# Adafruit_3_5_inch_480x320_Capacitive_Tou.net
KiCad netlist of a schematic drawn in EAGLE
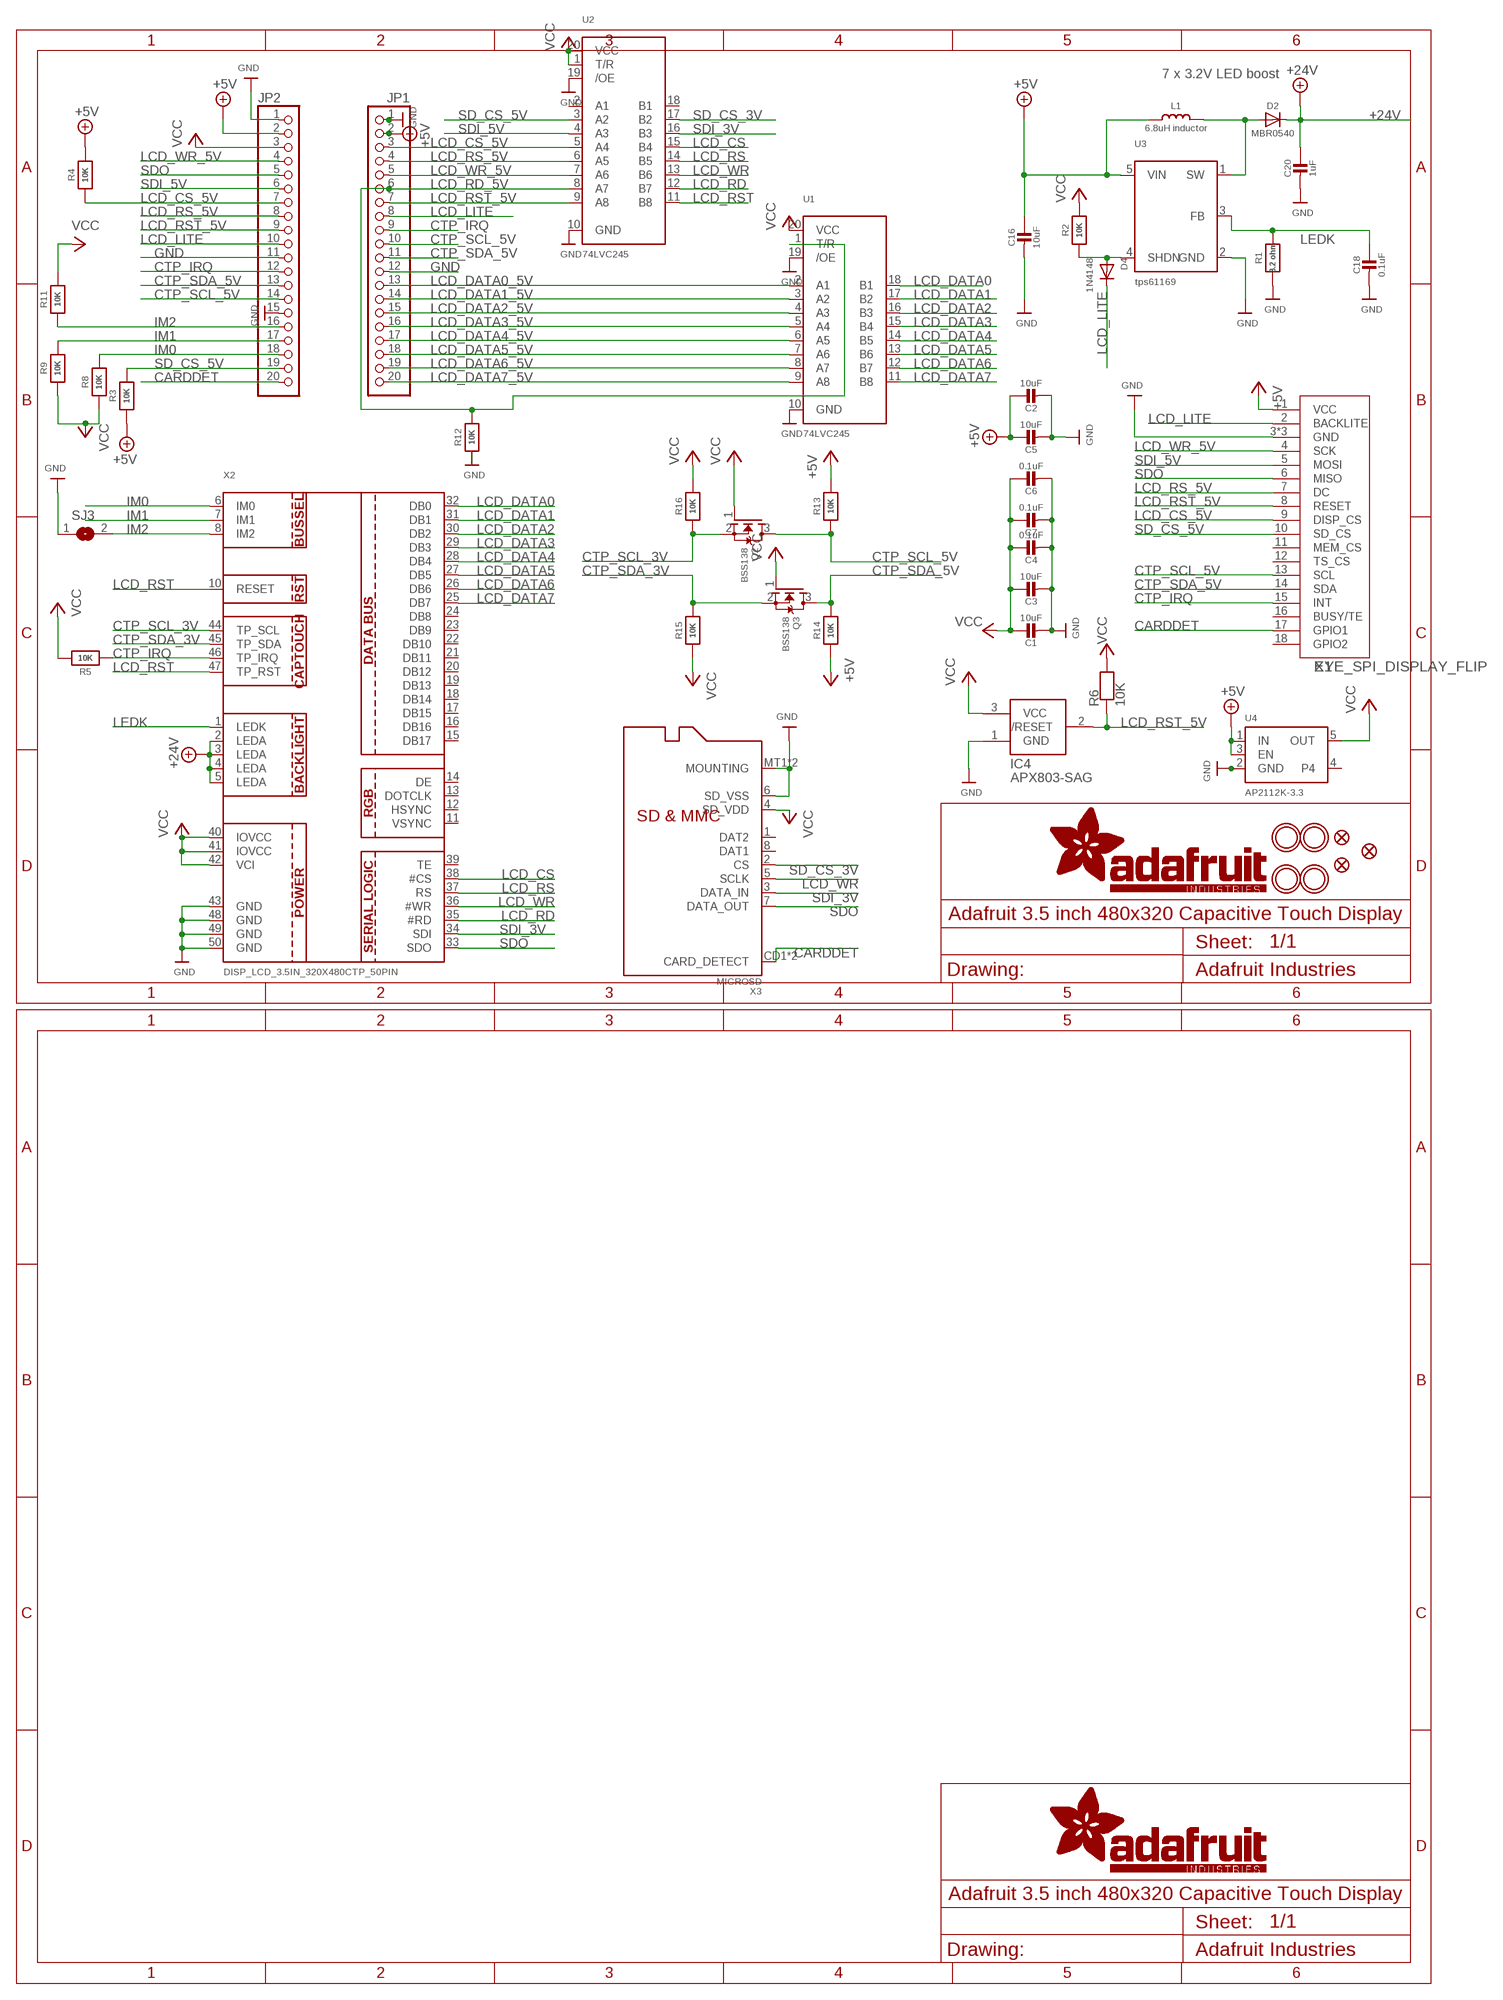
[diagram p0: schematic, sheet 1]

(export (version "E")
  (design (tool "Eeschema 10.0.6"))
  (components
    (comp (ref "C1")
      (value "10uF")
      (footprint "eagle-import:0805-NO")
      (libsource (lib "eagle-import") (part "CAP_CERAMIC0805-NOOUTLINE"))
    )
    (comp (ref "C2")
      (value "10uF")
      (footprint "eagle-import:0805-NO")
      (libsource (lib "eagle-import") (part "CAP_CERAMIC0805-NOOUTLINE"))
    )
    (comp (ref "C3")
      (value "10uF")
      (footprint "eagle-import:0805-NO")
      (libsource (lib "eagle-import") (part "CAP_CERAMIC0805-NOOUTLINE"))
    )
    (comp (ref "C4")
      (value "0.1uF")
      (footprint "eagle-import:0603-NO")
      (libsource (lib "eagle-import") (part "CAP_CERAMIC0603_NO"))
    )
    (comp (ref "C5")
      (value "10uF")
      (footprint "eagle-import:0805-NO")
      (libsource (lib "eagle-import") (part "CAP_CERAMIC0805-NOOUTLINE"))
    )
    (comp (ref "C6")
      (value "0.1uF")
      (footprint "eagle-import:0603-NO")
      (libsource (lib "eagle-import") (part "CAP_CERAMIC0603_NO"))
    )
    (comp (ref "C7")
      (value "0.1uF")
      (footprint "eagle-import:0603-NO")
      (libsource (lib "eagle-import") (part "CAP_CERAMIC0603_NO"))
    )
    (comp (ref "C16")
      (value "10uF")
      (footprint "eagle-import:0805-NO")
      (libsource (lib "eagle-import") (part "CAP_CERAMIC0805-NOOUTLINE"))
    )
    (comp (ref "C18")
      (value "0.1uF")
      (footprint "eagle-import:0603-NO")
      (libsource (lib "eagle-import") (part "CAP_CERAMIC0603_NO"))
    )
    (comp (ref "C20")
      (value "1uF")
      (footprint "eagle-import:0805-NO")
      (libsource (lib "eagle-import") (part "CAP_CERAMIC0805-NOOUTLINE"))
    )
    (comp (ref "D2")
      (value "MBR0540")
      (footprint "eagle-import:SOD-123")
      (libsource (lib "eagle-import") (part "microbuilder_DIODESOD-123"))
    )
    (comp (ref "D4")
      (value "1N4148")
      (footprint "eagle-import:SOD-323F")
      (libsource (lib "eagle-import") (part "DIODESOD-323F"))
    )
    (comp (ref "IC4")
      (value "APX803-SAG")
      (footprint "eagle-import:SOT23")
      (libsource (lib "eagle-import") (part "AXP083-SAG"))
    )
    (comp (ref "JP1")
      (value "HEADER-1X20ROUND")
      (footprint "eagle-import:1X20_ROUND")
      (libsource (lib "eagle-import") (part "HEADER-1X20ROUND"))
    )
    (comp (ref "JP2")
      (value "HEADER-1X20ROUND")
      (footprint "eagle-import:1X20_ROUND")
      (libsource (lib "eagle-import") (part "HEADER-1X20ROUND"))
    )
    (comp (ref "L1")
      (value "6.8uH inductor")
      (footprint "eagle-import:INDUCTOR_5X5MM_NR5040_NOTHERMALS")
      (libsource (lib "eagle-import") (part "INDUCTORNR5040"))
    )
    (comp (ref "Q2")
      (value "BSS138")
      (footprint "eagle-import:SOT23-WIDE")
      (libsource (lib "eagle-import") (part "MOSFET-NWIDE"))
    )
    (comp (ref "Q3")
      (value "BSS138")
      (footprint "eagle-import:SOT23-WIDE")
      (libsource (lib "eagle-import") (part "MOSFET-NWIDE"))
    )
    (comp (ref "R1")
      (value "8.2 ohm")
      (footprint "eagle-import:0603-NO")
      (libsource (lib "eagle-import") (part "RESISTOR_0603_NOOUT"))
    )
    (comp (ref "R2")
      (value "10K")
      (footprint "eagle-import:0603-NO")
      (libsource (lib "eagle-import") (part "RESISTOR_0603_NOOUT"))
    )
    (comp (ref "R3")
      (value "10K")
      (footprint "eagle-import:0603-NO")
      (libsource (lib "eagle-import") (part "RESISTOR_0603_NOOUT"))
    )
    (comp (ref "R4")
      (value "10K")
      (footprint "eagle-import:0603-NO")
      (libsource (lib "eagle-import") (part "RESISTOR_0603_NOOUT"))
    )
    (comp (ref "R5")
      (value "10K")
      (footprint "eagle-import:0603-NO")
      (libsource (lib "eagle-import") (part "RESISTOR_0603_NOOUT"))
    )
    (comp (ref "R6")
      (value "10K")
      (footprint "eagle-import:0603-NO")
      (libsource (lib "eagle-import") (part "RESISTOR_0603_NOOUT"))
    )
    (comp (ref "R8")
      (value "10K")
      (footprint "eagle-import:0603-NO")
      (libsource (lib "eagle-import") (part "RESISTOR_0603_NOOUT"))
    )
    (comp (ref "R9")
      (value "10K")
      (footprint "eagle-import:0603-NO")
      (libsource (lib "eagle-import") (part "RESISTOR_0603_NOOUT"))
    )
    (comp (ref "R11")
      (value "10K")
      (footprint "eagle-import:0603-NO")
      (libsource (lib "eagle-import") (part "RESISTOR_0603_NOOUT"))
    )
    (comp (ref "R12")
      (value "10K")
      (footprint "eagle-import:0603-NO")
      (libsource (lib "eagle-import") (part "RESISTOR_0603_NOOUT"))
    )
    (comp (ref "R13")
      (value "10K")
      (footprint "eagle-import:0603-NO")
      (libsource (lib "eagle-import") (part "RESISTOR_0603_NOOUT"))
    )
    (comp (ref "R14")
      (value "10K")
      (footprint "eagle-import:0603-NO")
      (libsource (lib "eagle-import") (part "RESISTOR_0603_NOOUT"))
    )
    (comp (ref "R15")
      (value "10K")
      (footprint "eagle-import:0603-NO")
      (libsource (lib "eagle-import") (part "RESISTOR_0603_NOOUT"))
    )
    (comp (ref "R16")
      (value "10K")
      (footprint "eagle-import:0603-NO")
      (libsource (lib "eagle-import") (part "RESISTOR_0603_NOOUT"))
    )
    (comp (ref "SJ3")
      (value "SOLDERJUMPER")
      (footprint "eagle-import:SOLDERJUMPER_ARROW_NOPASTE")
      (libsource (lib "eagle-import") (part "SOLDERJUMPER"))
    )
    (comp (ref "U$7")
      (value "MOUNTINGHOLE3.0THIN")
      (footprint "eagle-import:MOUNTINGHOLE_3.0_PLATEDTHIN")
      (libsource (lib "eagle-import") (part "MOUNTINGHOLE3.0THIN"))
    )
    (comp (ref "U$9")
      (value "FIDUCIAL_1MM")
      (footprint "eagle-import:FIDUCIAL_1MM")
      (libsource (lib "eagle-import") (part "FIDUCIAL_1MM"))
    )
    (comp (ref "U$11")
      (value "FIDUCIAL_1MM")
      (footprint "eagle-import:FIDUCIAL_1MM")
      (libsource (lib "eagle-import") (part "FIDUCIAL_1MM"))
    )
    (comp (ref "U$15")
      (value "MOUNTINGHOLE3.0THIN")
      (footprint "eagle-import:MOUNTINGHOLE_3.0_PLATEDTHIN")
      (libsource (lib "eagle-import") (part "MOUNTINGHOLE3.0THIN"))
    )
    (comp (ref "U$16")
      (value "MOUNTINGHOLE3.0THIN")
      (footprint "eagle-import:MOUNTINGHOLE_3.0_PLATEDTHIN")
      (libsource (lib "eagle-import") (part "MOUNTINGHOLE3.0THIN"))
    )
    (comp (ref "U$17")
      (value "MOUNTINGHOLE3.0THIN")
      (footprint "eagle-import:MOUNTINGHOLE_3.0_PLATEDTHIN")
      (libsource (lib "eagle-import") (part "MOUNTINGHOLE3.0THIN"))
    )
    (comp (ref "U$23")
      (value "FIDUCIAL_1MM")
      (footprint "eagle-import:FIDUCIAL_1MM")
      (libsource (lib "eagle-import") (part "FIDUCIAL_1MM"))
    )
    (comp (ref "U1")
      (value "74LVC245")
      (footprint "eagle-import:TSSOP20")
      (libsource (lib "eagle-import") (part "74LCX245_TSSOP20"))
    )
    (comp (ref "U2")
      (value "74LVC245")
      (footprint "eagle-import:TSSOP20")
      (libsource (lib "eagle-import") (part "74LCX245_TSSOP20"))
    )
    (comp (ref "U3")
      (value "tps61169")
      (footprint "eagle-import:SC70-5")
      (libsource (lib "eagle-import") (part "VREG_BOOST_5PIN_SC70"))
    )
    (comp (ref "U4")
      (value "AP2112K-3.3")
      (footprint "eagle-import:SOT23-5")
      (libsource (lib "eagle-import") (part "VREG_SOT23-5"))
    )
    (comp (ref "X1")
      (value "EYE_SPI_DISPLAY_FLIP")
      (footprint "eagle-import:EYE_SPI_DISPLAY_BOTCONTACT")
      (libsource (lib "eagle-import") (part "EYE_SPI_DISPLAY_FLIP"))
    )
    (comp (ref "X2")
      (value "DISP_LCD_3.5IN_320X480CTP_50PIN")
      (footprint "eagle-import:TFT_3.5IN_320X480_50PIN")
      (libsource (lib "eagle-import") (part "DISP_LCD_3.5IN_320X480CTP_50PIN"))
    )
    (comp (ref "X3")
      (value "MICROSD")
      (footprint "eagle-import:MICROSD")
      (libsource (lib "eagle-import") (part "MICROSD"))
    )
  )
  (nets
    (net (code "1") (name "+5V") (class "Default")
      (node (ref "C16") (pin "1") (pinfunction "1_1") (pintype "passive"))
      (node (ref "C2") (pin "1") (pinfunction "1_1") (pintype "passive"))
      (node (ref "C5") (pin "1") (pinfunction "1_1") (pintype "passive"))
      (node (ref "JP1") (pin "2") (pinfunction "2_2") (pintype "passive"))
      (node (ref "JP2") (pin "2") (pinfunction "2_2") (pintype "passive"))
      (node (ref "L1") (pin "P$1") (pinfunction "1_P$1") (pintype "passive"))
      (node (ref "R13") (pin "2") (pinfunction "2_2") (pintype "passive"))
      (node (ref "R14") (pin "1") (pinfunction "1_1") (pintype "passive"))
      (node (ref "R3") (pin "1") (pinfunction "1_1") (pintype "passive"))
      (node (ref "R4") (pin "2") (pinfunction "2_2") (pintype "passive"))
      (node (ref "U3") (pin "5") (pinfunction "VIN_5") (pintype "bidirectional"))
      (node (ref "U4") (pin "1") (pinfunction "IN_1") (pintype "power_in"))
      (node (ref "U4") (pin "3") (pinfunction "EN_3") (pintype "input"))
      (node (ref "X1") (pin "1") (pinfunction "VCC_1") (pintype "power_in"))
    )
    (net (code "2") (name "+24V") (class "Default")
      (node (ref "C20") (pin "1") (pinfunction "1_1") (pintype "passive"))
      (node (ref "D2") (pin "C") (pinfunction "C_C") (pintype "passive"))
      (node (ref "X2") (pin "2") (pinfunction "LEDA_2") (pintype "bidirectional"))
      (node (ref "X2") (pin "3") (pinfunction "LEDA_3") (pintype "bidirectional"))
      (node (ref "X2") (pin "4") (pinfunction "LEDA_4") (pintype "bidirectional"))
      (node (ref "X2") (pin "5") (pinfunction "LEDA_5") (pintype "bidirectional"))
    )
    (net (code "3") (name "/CARDDET") (class "Default")
      (node (ref "JP2") (pin "20") (pinfunction "20_20") (pintype "passive"))
      (node (ref "X1") (pin "17") (pinfunction "GPIO1_17") (pintype "passive"))
      (node (ref "X3") (pin "CD1") (pinfunction "CARD_DETECT_CD1") (pintype "passive"))
      (node (ref "X3") (pin "CD2") (pinfunction "CARD_DETECT_CD2") (pintype "passive"))
    )
    (net (code "4") (name "/CTP_IRQ") (class "Default")
      (node (ref "JP1") (pin "9") (pinfunction "9_9") (pintype "passive"))
      (node (ref "JP2") (pin "12") (pinfunction "12_12") (pintype "passive"))
      (node (ref "R5") (pin "1") (pinfunction "1_1") (pintype "passive"))
      (node (ref "X1") (pin "15") (pinfunction "INT_15") (pintype "output"))
      (node (ref "X2") (pin "46") (pinfunction "TP_IRQ_46") (pintype "bidirectional"))
    )
    (net (code "5") (name "/CTP_SCL_3V") (class "Default")
      (node (ref "Q2") (pin "2") (pinfunction "S_2") (pintype "bidirectional"))
      (node (ref "R16") (pin "1") (pinfunction "1_1") (pintype "passive"))
      (node (ref "X2") (pin "44") (pinfunction "TP_SCL_44") (pintype "bidirectional"))
    )
    (net (code "6") (name "/CTP_SCL_5V") (class "Default")
      (node (ref "JP1") (pin "10") (pinfunction "10_10") (pintype "passive"))
      (node (ref "JP2") (pin "14") (pinfunction "14_14") (pintype "passive"))
      (node (ref "Q2") (pin "3") (pinfunction "D_3") (pintype "bidirectional"))
      (node (ref "R13") (pin "1") (pinfunction "1_1") (pintype "passive"))
      (node (ref "X1") (pin "13") (pinfunction "SCL_13") (pintype "input"))
    )
    (net (code "7") (name "/CTP_SDA_3V") (class "Default")
      (node (ref "Q3") (pin "2") (pinfunction "S_2") (pintype "bidirectional"))
      (node (ref "R15") (pin "2") (pinfunction "2_2") (pintype "passive"))
      (node (ref "X2") (pin "45") (pinfunction "TP_SDA_45") (pintype "bidirectional"))
    )
    (net (code "8") (name "/CTP_SDA_5V") (class "Default")
      (node (ref "JP1") (pin "11") (pinfunction "11_11") (pintype "passive"))
      (node (ref "JP2") (pin "13") (pinfunction "13_13") (pintype "passive"))
      (node (ref "Q3") (pin "3") (pinfunction "D_3") (pintype "bidirectional"))
      (node (ref "R14") (pin "2") (pinfunction "2_2") (pintype "passive"))
      (node (ref "X1") (pin "14") (pinfunction "SDA_14") (pintype "bidirectional"))
    )
    (net (code "9") (name "/IM0") (class "Default")
      (node (ref "JP2") (pin "18") (pinfunction "18_18") (pintype "passive"))
      (node (ref "R8") (pin "2") (pinfunction "2_2") (pintype "passive"))
      (node (ref "X2") (pin "6") (pinfunction "IM0_6") (pintype "bidirectional"))
    )
    (net (code "10") (name "/IM1") (class "Default")
      (node (ref "JP2") (pin "17") (pinfunction "17_17") (pintype "passive"))
      (node (ref "R9") (pin "2") (pinfunction "2_2") (pintype "passive"))
      (node (ref "X2") (pin "7") (pinfunction "IM1_7") (pintype "bidirectional"))
    )
    (net (code "11") (name "/IM2") (class "Default")
      (node (ref "JP2") (pin "16") (pinfunction "16_16") (pintype "passive"))
      (node (ref "R11") (pin "1") (pinfunction "1_1") (pintype "passive"))
      (node (ref "SJ3") (pin "2") (pinfunction "2_2") (pintype "passive"))
      (node (ref "X2") (pin "8") (pinfunction "IM2_8") (pintype "bidirectional"))
    )
    (net (code "12") (name "/LCD_CS") (class "Default")
      (node (ref "U2") (pin "15") (pinfunction "B4_15") (pintype "bidirectional"))
      (node (ref "X2") (pin "38") (pinfunction "#CS_38") (pintype "bidirectional"))
    )
    (net (code "13") (name "/LCD_CS_5V") (class "Default")
      (node (ref "JP1") (pin "3") (pinfunction "3_3") (pintype "passive"))
      (node (ref "JP2") (pin "7") (pinfunction "7_7") (pintype "passive"))
      (node (ref "R4") (pin "1") (pinfunction "1_1") (pintype "passive"))
      (node (ref "U2") (pin "5") (pinfunction "A4_5") (pintype "bidirectional"))
      (node (ref "X1") (pin "9") (pinfunction "DISP_CS_9") (pintype "input"))
    )
    (net (code "14") (name "/LCD_DATA0") (class "Default")
      (node (ref "U1") (pin "18") (pinfunction "B1_18") (pintype "bidirectional"))
      (node (ref "X2") (pin "32") (pinfunction "DB0_32") (pintype "bidirectional"))
    )
    (net (code "15") (name "/LCD_DATA0_5V") (class "Default")
      (node (ref "JP1") (pin "13") (pinfunction "13_13") (pintype "passive"))
      (node (ref "U1") (pin "2") (pinfunction "A1_2") (pintype "bidirectional"))
    )
    (net (code "16") (name "/LCD_DATA1") (class "Default")
      (node (ref "U1") (pin "17") (pinfunction "B2_17") (pintype "bidirectional"))
      (node (ref "X2") (pin "31") (pinfunction "DB1_31") (pintype "bidirectional"))
    )
    (net (code "17") (name "/LCD_DATA1_5V") (class "Default")
      (node (ref "JP1") (pin "14") (pinfunction "14_14") (pintype "passive"))
      (node (ref "U1") (pin "3") (pinfunction "A2_3") (pintype "bidirectional"))
    )
    (net (code "18") (name "/LCD_DATA2") (class "Default")
      (node (ref "U1") (pin "16") (pinfunction "B3_16") (pintype "bidirectional"))
      (node (ref "X2") (pin "30") (pinfunction "DB2_30") (pintype "bidirectional"))
    )
    (net (code "19") (name "/LCD_DATA2_5V") (class "Default")
      (node (ref "JP1") (pin "15") (pinfunction "15_15") (pintype "passive"))
      (node (ref "U1") (pin "4") (pinfunction "A3_4") (pintype "bidirectional"))
    )
    (net (code "20") (name "/LCD_DATA3") (class "Default")
      (node (ref "U1") (pin "15") (pinfunction "B4_15") (pintype "bidirectional"))
      (node (ref "X2") (pin "29") (pinfunction "DB3_29") (pintype "bidirectional"))
    )
    (net (code "21") (name "/LCD_DATA3_5V") (class "Default")
      (node (ref "JP1") (pin "16") (pinfunction "16_16") (pintype "passive"))
      (node (ref "U1") (pin "5") (pinfunction "A4_5") (pintype "bidirectional"))
    )
    (net (code "22") (name "/LCD_DATA4") (class "Default")
      (node (ref "U1") (pin "14") (pinfunction "B5_14") (pintype "bidirectional"))
      (node (ref "X2") (pin "28") (pinfunction "DB4_28") (pintype "bidirectional"))
    )
    (net (code "23") (name "/LCD_DATA4_5V") (class "Default")
      (node (ref "JP1") (pin "17") (pinfunction "17_17") (pintype "passive"))
      (node (ref "U1") (pin "6") (pinfunction "A5_6") (pintype "bidirectional"))
    )
    (net (code "24") (name "/LCD_DATA5") (class "Default")
      (node (ref "U1") (pin "13") (pinfunction "B6_13") (pintype "bidirectional"))
      (node (ref "X2") (pin "27") (pinfunction "DB5_27") (pintype "bidirectional"))
    )
    (net (code "25") (name "/LCD_DATA5_5V") (class "Default")
      (node (ref "JP1") (pin "18") (pinfunction "18_18") (pintype "passive"))
      (node (ref "U1") (pin "7") (pinfunction "A6_7") (pintype "bidirectional"))
    )
    (net (code "26") (name "/LCD_DATA6") (class "Default")
      (node (ref "U1") (pin "12") (pinfunction "B7_12") (pintype "bidirectional"))
      (node (ref "X2") (pin "26") (pinfunction "DB6_26") (pintype "bidirectional"))
    )
    (net (code "27") (name "/LCD_DATA6_5V") (class "Default")
      (node (ref "JP1") (pin "19") (pinfunction "19_19") (pintype "passive"))
      (node (ref "U1") (pin "8") (pinfunction "A7_8") (pintype "bidirectional"))
    )
    (net (code "28") (name "/LCD_DATA7") (class "Default")
      (node (ref "U1") (pin "11") (pinfunction "B8_11") (pintype "bidirectional"))
      (node (ref "X2") (pin "25") (pinfunction "DB7_25") (pintype "bidirectional"))
    )
    (net (code "29") (name "/LCD_DATA7_5V") (class "Default")
      (node (ref "JP1") (pin "20") (pinfunction "20_20") (pintype "passive"))
      (node (ref "U1") (pin "9") (pinfunction "A8_9") (pintype "bidirectional"))
    )
    (net (code "30") (name "/LCD_LITE") (class "Default")
      (node (ref "D4") (pin "C") (pinfunction "C_C") (pintype "passive"))
      (node (ref "JP1") (pin "8") (pinfunction "8_8") (pintype "passive"))
      (node (ref "JP2") (pin "10") (pinfunction "10_10") (pintype "passive"))
      (node (ref "X1") (pin "2") (pinfunction "BACKLITE_2") (pintype "input"))
    )
    (net (code "31") (name "/LCD_RD") (class "Default")
      (node (ref "U2") (pin "12") (pinfunction "B7_12") (pintype "bidirectional"))
      (node (ref "X2") (pin "35") (pinfunction "#RD_35") (pintype "bidirectional"))
    )
    (net (code "32") (name "/LCD_RD_5V") (class "Default")
      (node (ref "JP1") (pin "6") (pinfunction "6_6") (pintype "passive"))
      (node (ref "R12") (pin "2") (pinfunction "2_2") (pintype "passive"))
      (node (ref "U1") (pin "1") (pinfunction "T/R_1") (pintype "bidirectional"))
      (node (ref "U2") (pin "8") (pinfunction "A7_8") (pintype "bidirectional"))
    )
    (net (code "33") (name "/LCD_RS") (class "Default")
      (node (ref "U2") (pin "14") (pinfunction "B5_14") (pintype "bidirectional"))
      (node (ref "X2") (pin "37") (pinfunction "RS_37") (pintype "bidirectional"))
    )
    (net (code "34") (name "/LCD_RST") (class "Default")
      (node (ref "U2") (pin "11") (pinfunction "B8_11") (pintype "bidirectional"))
      (node (ref "X2") (pin "10") (pinfunction "RESET_10") (pintype "bidirectional"))
      (node (ref "X2") (pin "47") (pinfunction "TP_RST_47") (pintype "bidirectional"))
    )
    (net (code "35") (name "/LCD_RST_5V") (class "Default")
      (node (ref "IC4") (pin "2") (pinfunction "/RESET_2") (pintype "output"))
      (node (ref "JP1") (pin "7") (pinfunction "7_7") (pintype "passive"))
      (node (ref "JP2") (pin "9") (pinfunction "9_9") (pintype "passive"))
      (node (ref "R6") (pin "1") (pinfunction "1_1") (pintype "passive"))
      (node (ref "U2") (pin "9") (pinfunction "A8_9") (pintype "bidirectional"))
      (node (ref "X1") (pin "8") (pinfunction "RESET_8") (pintype "input"))
    )
    (net (code "36") (name "/LCD_RS_5V") (class "Default")
      (node (ref "JP1") (pin "4") (pinfunction "4_4") (pintype "passive"))
      (node (ref "JP2") (pin "8") (pinfunction "8_8") (pintype "passive"))
      (node (ref "U2") (pin "6") (pinfunction "A5_6") (pintype "bidirectional"))
      (node (ref "X1") (pin "7") (pinfunction "DC_7") (pintype "input"))
    )
    (net (code "37") (name "/LCD_WR") (class "Default")
      (node (ref "U2") (pin "13") (pinfunction "B6_13") (pintype "bidirectional"))
      (node (ref "X2") (pin "36") (pinfunction "#WR_36") (pintype "bidirectional"))
      (node (ref "X3") (pin "5") (pinfunction "SCLK_5") (pintype "input"))
    )
    (net (code "38") (name "/LCD_WR_5V") (class "Default")
      (node (ref "JP1") (pin "5") (pinfunction "5_5") (pintype "passive"))
      (node (ref "JP2") (pin "4") (pinfunction "4_4") (pintype "passive"))
      (node (ref "U2") (pin "7") (pinfunction "A6_7") (pintype "bidirectional"))
      (node (ref "X1") (pin "4") (pinfunction "SCK_4") (pintype "input"))
    )
    (net (code "39") (name "/LEDK") (class "Default")
      (node (ref "C18") (pin "1") (pinfunction "1_1") (pintype "passive"))
      (node (ref "R1") (pin "2") (pinfunction "2_2") (pintype "passive"))
      (node (ref "U3") (pin "3") (pinfunction "FB_3") (pintype "bidirectional"))
      (node (ref "X2") (pin "1") (pinfunction "LEDK_1") (pintype "bidirectional"))
    )
    (net (code "40") (name "/SDI_3V") (class "Default")
      (node (ref "U2") (pin "16") (pinfunction "B3_16") (pintype "bidirectional"))
      (node (ref "X2") (pin "34") (pinfunction "SDI_34") (pintype "bidirectional"))
      (node (ref "X3") (pin "3") (pinfunction "DATA_IN_3") (pintype "input"))
    )
    (net (code "41") (name "/SDI_5V") (class "Default")
      (node (ref "JP2") (pin "6") (pinfunction "6_6") (pintype "passive"))
      (node (ref "U2") (pin "4") (pinfunction "A3_4") (pintype "bidirectional"))
      (node (ref "X1") (pin "5") (pinfunction "MOSI_5") (pintype "input"))
    )
    (net (code "42") (name "/SDO") (class "Default")
      (node (ref "JP2") (pin "5") (pinfunction "5_5") (pintype "passive"))
      (node (ref "X1") (pin "6") (pinfunction "MISO_6") (pintype "output"))
      (node (ref "X2") (pin "33") (pinfunction "SDO_33") (pintype "bidirectional"))
      (node (ref "X3") (pin "7") (pinfunction "DATA_OUT_7") (pintype "output"))
    )
    (net (code "43") (name "/SD_CS_3V") (class "Default")
      (node (ref "U2") (pin "17") (pinfunction "B2_17") (pintype "bidirectional"))
      (node (ref "X3") (pin "2") (pinfunction "CS_2") (pintype "input"))
    )
    (net (code "44") (name "/SD_CS_5V") (class "Default")
      (node (ref "JP2") (pin "19") (pinfunction "19_19") (pintype "passive"))
      (node (ref "R3") (pin "2") (pinfunction "2_2") (pintype "passive"))
      (node (ref "U2") (pin "3") (pinfunction "A2_3") (pintype "bidirectional"))
      (node (ref "X1") (pin "10") (pinfunction "SD_CS_10") (pintype "input"))
    )
    (net (code "45") (name "GND") (class "Default")
      (node (ref "C1") (pin "2") (pinfunction "2_2") (pintype "passive"))
      (node (ref "C16") (pin "2") (pinfunction "2_2") (pintype "passive"))
      (node (ref "C18") (pin "2") (pinfunction "2_2") (pintype "passive"))
      (node (ref "C2") (pin "2") (pinfunction "2_2") (pintype "passive"))
      (node (ref "C20") (pin "2") (pinfunction "2_2") (pintype "passive"))
      (node (ref "C3") (pin "2") (pinfunction "2_2") (pintype "passive"))
      (node (ref "C4") (pin "2") (pinfunction "2_2") (pintype "passive"))
      (node (ref "C5") (pin "2") (pinfunction "2_2") (pintype "passive"))
      (node (ref "C6") (pin "2") (pinfunction "2_2") (pintype "passive"))
      (node (ref "C7") (pin "2") (pinfunction "2_2") (pintype "passive"))
      (node (ref "IC4") (pin "1") (pinfunction "GND_1") (pintype "power_in"))
      (node (ref "JP1") (pin "1") (pinfunction "1_1") (pintype "passive"))
      (node (ref "JP1") (pin "12") (pinfunction "12_12") (pintype "passive"))
      (node (ref "JP2") (pin "1") (pinfunction "1_1") (pintype "passive"))
      (node (ref "JP2") (pin "11") (pinfunction "11_11") (pintype "passive"))
      (node (ref "JP2") (pin "15") (pinfunction "15_15") (pintype "passive"))
      (node (ref "R1") (pin "1") (pinfunction "1_1") (pintype "passive"))
      (node (ref "R12") (pin "1") (pinfunction "1_1") (pintype "passive"))
      (node (ref "SJ3") (pin "1") (pinfunction "1_1") (pintype "passive"))
      (node (ref "U1") (pin "10") (pinfunction "GND_10") (pintype "bidirectional"))
      (node (ref "U1") (pin "19") (pinfunction "/OE_19") (pintype "bidirectional"))
      (node (ref "U2") (pin "10") (pinfunction "GND_10") (pintype "bidirectional"))
      (node (ref "U2") (pin "19") (pinfunction "/OE_19") (pintype "bidirectional"))
      (node (ref "U3") (pin "2") (pinfunction "GND_2") (pintype "bidirectional"))
      (node (ref "U4") (pin "2") (pinfunction "GND_2") (pintype "power_in"))
      (node (ref "X1") (pin "3") (pinfunction "GND_3") (pintype "power_in"))
      (node (ref "X1") (pin "SUPPORT1") (pinfunction "GND_SUPPORT1") (pintype "power_in"))
      (node (ref "X1") (pin "SUPPORT2") (pinfunction "GND_SUPPORT2") (pintype "power_in"))
      (node (ref "X2") (pin "43") (pinfunction "GND_43") (pintype "bidirectional"))
      (node (ref "X2") (pin "48") (pinfunction "GND_48") (pintype "bidirectional"))
      (node (ref "X2") (pin "49") (pinfunction "GND_49") (pintype "bidirectional"))
      (node (ref "X2") (pin "50") (pinfunction "GND_50") (pintype "bidirectional"))
      (node (ref "X3") (pin "6") (pinfunction "SD_VSS_6") (pintype "power_in"))
      (node (ref "X3") (pin "MT1") (pinfunction "MOUNTING_MT1") (pintype "passive"))
      (node (ref "X3") (pin "MT2") (pinfunction "MOUNTING_MT2") (pintype "passive"))
    )
    (net (code "46") (name "Net-(L1-2)") (class "Default")
      (node (ref "D2") (pin "A") (pinfunction "A_A") (pintype "passive"))
      (node (ref "L1") (pin "P$2") (pinfunction "2_P$2") (pintype "passive"))
      (node (ref "U3") (pin "1") (pinfunction "SW_1") (pintype "bidirectional"))
    )
    (net (code "47") (name "Net-(U3-SHDN)") (class "Default")
      (node (ref "D4") (pin "A") (pinfunction "A_A") (pintype "passive"))
      (node (ref "R2") (pin "1") (pinfunction "1_1") (pintype "passive"))
      (node (ref "U3") (pin "4") (pinfunction "SHDN_4") (pintype "bidirectional"))
    )
    (net (code "48") (name "VCC") (class "Default")
      (node (ref "C1") (pin "1") (pinfunction "1_1") (pintype "passive"))
      (node (ref "C3") (pin "1") (pinfunction "1_1") (pintype "passive"))
      (node (ref "C4") (pin "1") (pinfunction "1_1") (pintype "passive"))
      (node (ref "C6") (pin "1") (pinfunction "1_1") (pintype "passive"))
      (node (ref "C7") (pin "1") (pinfunction "1_1") (pintype "passive"))
      (node (ref "IC4") (pin "3") (pinfunction "VCC_3") (pintype "power_in"))
      (node (ref "JP2") (pin "3") (pinfunction "3_3") (pintype "passive"))
      (node (ref "Q2") (pin "1") (pinfunction "G_1") (pintype "bidirectional"))
      (node (ref "Q3") (pin "1") (pinfunction "G_1") (pintype "bidirectional"))
      (node (ref "R11") (pin "2") (pinfunction "2_2") (pintype "passive"))
      (node (ref "R15") (pin "1") (pinfunction "1_1") (pintype "passive"))
      (node (ref "R16") (pin "2") (pinfunction "2_2") (pintype "passive"))
      (node (ref "R2") (pin "2") (pinfunction "2_2") (pintype "passive"))
      (node (ref "R5") (pin "2") (pinfunction "2_2") (pintype "passive"))
      (node (ref "R6") (pin "2") (pinfunction "2_2") (pintype "passive"))
      (node (ref "R8") (pin "1") (pinfunction "1_1") (pintype "passive"))
      (node (ref "R9") (pin "1") (pinfunction "1_1") (pintype "passive"))
      (node (ref "U1") (pin "20") (pinfunction "VCC_20") (pintype "bidirectional"))
      (node (ref "U2") (pin "1") (pinfunction "T/R_1") (pintype "bidirectional"))
      (node (ref "U2") (pin "20") (pinfunction "VCC_20") (pintype "bidirectional"))
      (node (ref "U4") (pin "5") (pinfunction "OUT_5") (pintype "power_in"))
      (node (ref "X2") (pin "40") (pinfunction "IOVCC_40") (pintype "bidirectional"))
      (node (ref "X2") (pin "41") (pinfunction "IOVCC_41") (pintype "bidirectional"))
      (node (ref "X2") (pin "42") (pinfunction "VCI_42") (pintype "bidirectional"))
      (node (ref "X3") (pin "4") (pinfunction "SD_VDD_4") (pintype "power_in"))
    )
    (net (code "49") (name "unconnected-(U2-A1-Pad2)") (class "Default")
      (node (ref "U2") (pin "2") (pinfunction "A1_2") (pintype "bidirectional"))
    )
    (net (code "50") (name "unconnected-(U2-B1-Pad18)") (class "Default")
      (node (ref "U2") (pin "18") (pinfunction "B1_18") (pintype "bidirectional"))
    )
    (net (code "51") (name "unconnected-(U4-P4-Pad4)") (class "Default")
      (node (ref "U4") (pin "4") (pinfunction "P4_4") (pintype "bidirectional"))
    )
    (net (code "52") (name "unconnected-(X1-BUSY{slash}TE-Pad16)") (class "Default")
      (node (ref "X1") (pin "16") (pinfunction "BUSY/TE_16") (pintype "output"))
    )
    (net (code "53") (name "unconnected-(X1-GPIO2-Pad18)") (class "Default")
      (node (ref "X1") (pin "18") (pinfunction "GPIO2_18") (pintype "passive"))
    )
    (net (code "54") (name "unconnected-(X1-MEM_CS-Pad11)") (class "Default")
      (node (ref "X1") (pin "11") (pinfunction "MEM_CS_11") (pintype "input"))
    )
    (net (code "55") (name "unconnected-(X1-TS_CS-Pad12)") (class "Default")
      (node (ref "X1") (pin "12") (pinfunction "TS_CS_12") (pintype "input"))
    )
    (net (code "56") (name "unconnected-(X2-DB8-Pad24)") (class "Default")
      (node (ref "X2") (pin "24") (pinfunction "DB8_24") (pintype "bidirectional"))
    )
    (net (code "57") (name "unconnected-(X2-DB9-Pad23)") (class "Default")
      (node (ref "X2") (pin "23") (pinfunction "DB9_23") (pintype "bidirectional"))
    )
    (net (code "58") (name "unconnected-(X2-DB10-Pad22)") (class "Default")
      (node (ref "X2") (pin "22") (pinfunction "DB10_22") (pintype "bidirectional"))
    )
    (net (code "59") (name "unconnected-(X2-DB11-Pad21)") (class "Default")
      (node (ref "X2") (pin "21") (pinfunction "DB11_21") (pintype "bidirectional"))
    )
    (net (code "60") (name "unconnected-(X2-DB12-Pad20)") (class "Default")
      (node (ref "X2") (pin "20") (pinfunction "DB12_20") (pintype "bidirectional"))
    )
    (net (code "61") (name "unconnected-(X2-DB13-Pad19)") (class "Default")
      (node (ref "X2") (pin "19") (pinfunction "DB13_19") (pintype "bidirectional"))
    )
    (net (code "62") (name "unconnected-(X2-DB14-Pad18)") (class "Default")
      (node (ref "X2") (pin "18") (pinfunction "DB14_18") (pintype "bidirectional"))
    )
    (net (code "63") (name "unconnected-(X2-DB15-Pad17)") (class "Default")
      (node (ref "X2") (pin "17") (pinfunction "DB15_17") (pintype "bidirectional"))
    )
    (net (code "64") (name "unconnected-(X2-DB16-Pad16)") (class "Default")
      (node (ref "X2") (pin "16") (pinfunction "DB16_16") (pintype "bidirectional"))
    )
    (net (code "65") (name "unconnected-(X2-DB17-Pad15)") (class "Default")
      (node (ref "X2") (pin "15") (pinfunction "DB17_15") (pintype "bidirectional"))
    )
    (net (code "66") (name "unconnected-(X2-DE-Pad14)") (class "Default")
      (node (ref "X2") (pin "14") (pinfunction "DE_14") (pintype "bidirectional"))
    )
    (net (code "67") (name "unconnected-(X2-DOTCLK-Pad13)") (class "Default")
      (node (ref "X2") (pin "13") (pinfunction "DOTCLK_13") (pintype "bidirectional"))
    )
    (net (code "68") (name "unconnected-(X2-HSYNC-Pad12)") (class "Default")
      (node (ref "X2") (pin "12") (pinfunction "HSYNC_12") (pintype "bidirectional"))
    )
    (net (code "69") (name "unconnected-(X2-TE-Pad39)") (class "Default")
      (node (ref "X2") (pin "39") (pinfunction "TE_39") (pintype "bidirectional"))
    )
    (net (code "70") (name "unconnected-(X2-VSYNC-Pad11)") (class "Default")
      (node (ref "X2") (pin "11") (pinfunction "VSYNC_11") (pintype "bidirectional"))
    )
    (net (code "71") (name "unconnected-(X3-DAT1-Pad8)") (class "Default")
      (node (ref "X3") (pin "8") (pinfunction "DAT1_8") (pintype "bidirectional"))
    )
    (net (code "72") (name "unconnected-(X3-DAT2-Pad1)") (class "Default")
      (node (ref "X3") (pin "1") (pinfunction "DAT2_1") (pintype "bidirectional"))
    )
  )
)
